# WIFI.net
KiCad netlist of a schematic drawn in Altium Designer
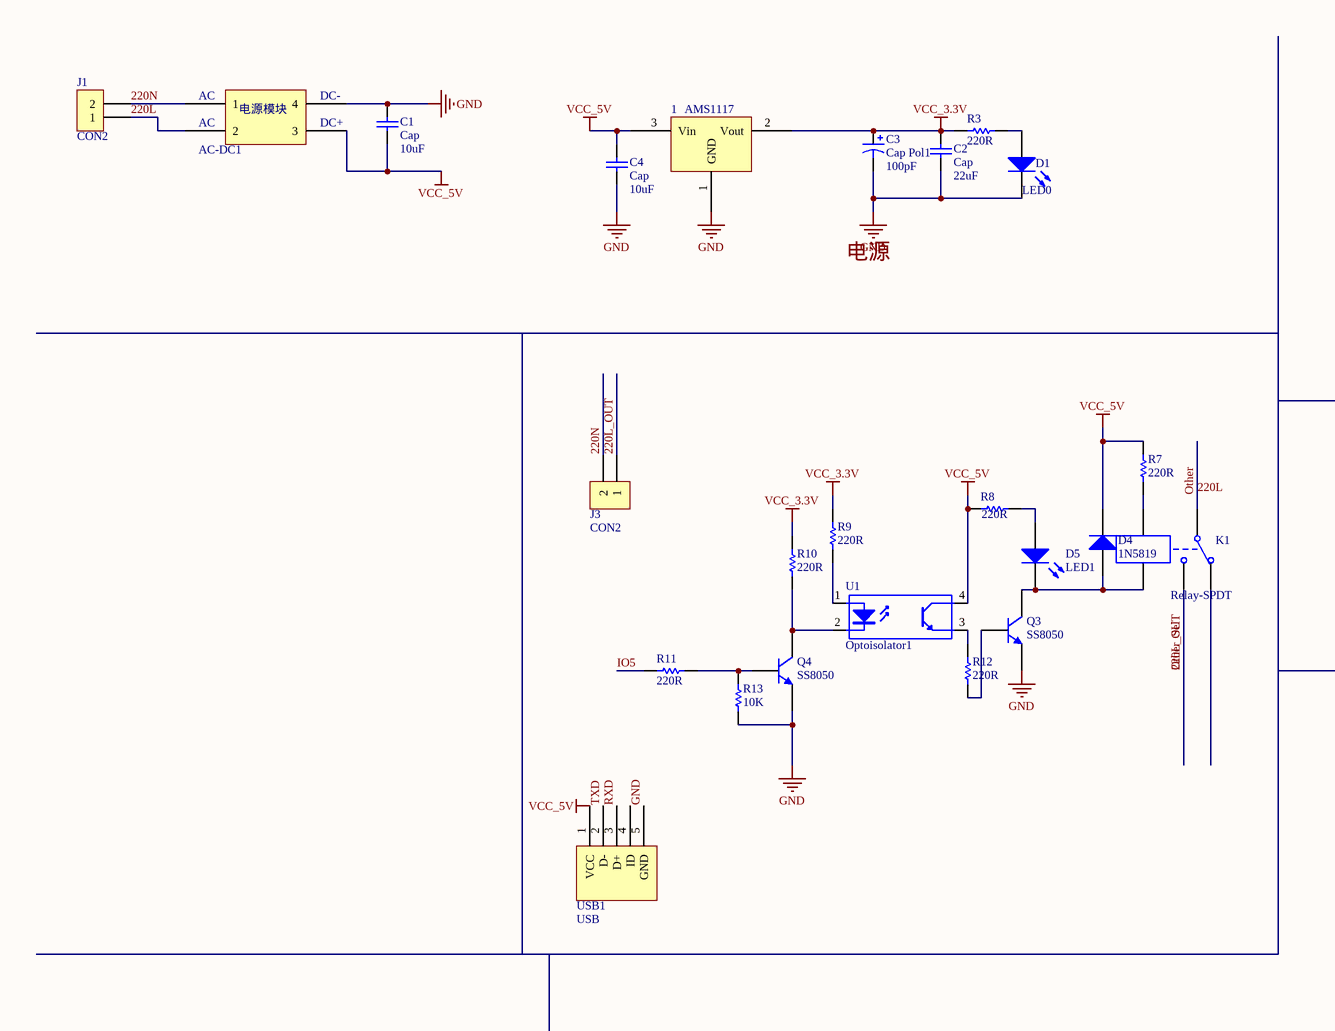
[diagram p0: WIFI.SchDoc, left]
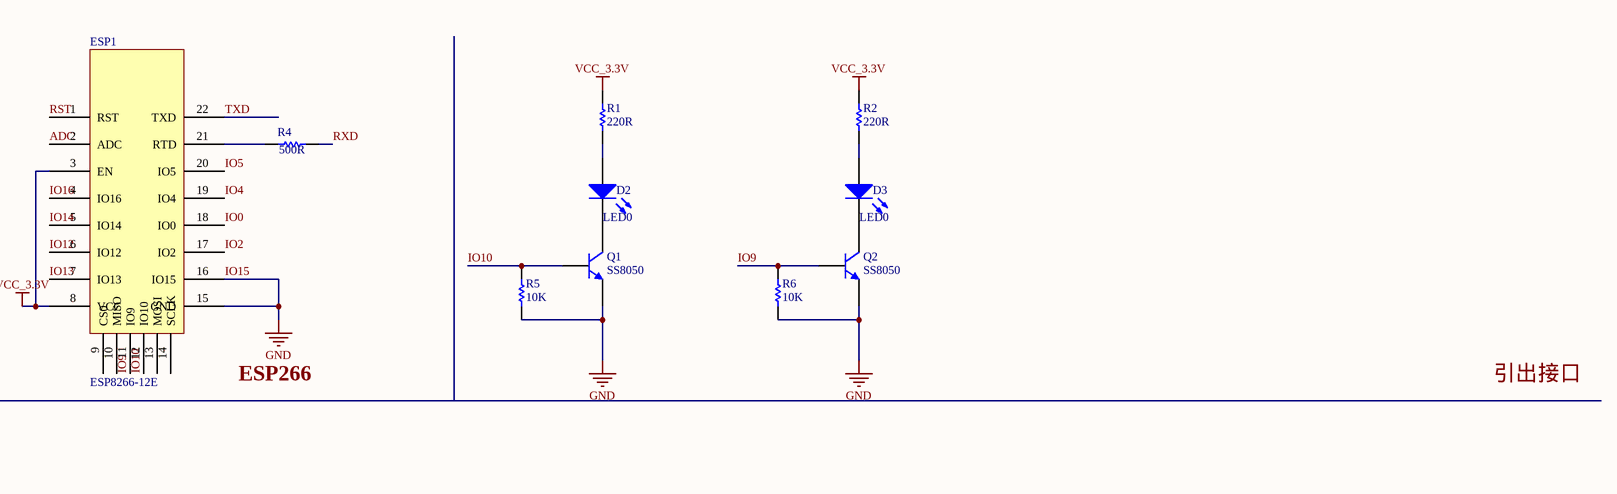
[diagram p1: WIFI.SchDoc, right]

(export (version "E")
  (design (tool "Eeschema 10.0.6"))
  (components
    (comp (ref "1") (value "AMS1117") (footprint "SOT223") (libsource (lib "开关电路") (part "AMS1117")))
    (comp (ref "AC-DC1") (value "220—5") (footprint "POWER-220_5") (libsource (lib "开关电路") (part "220—5")))
    (comp (ref "C1")
      (value "Cap")
      (footprint "CAP-E SMD 8X8")
      (description "Capacitor")
      (fields (field (name "ALTIUM_VALUE") "10uF") (field (name "PUBLISHER") "Altium Limited"))
      (libsource (lib "Miscellaneous Devices0") (part "Cap"))
    )
    (comp (ref "C2")
      (value "Cap")
      (footprint "1206")
      (description "Capacitor")
      (fields (field (name "ALTIUM_VALUE") "22uF") (field (name "PUBLISHER") "Altium Limited"))
      (libsource (lib "Miscellaneous Devices0") (part "Cap"))
    )
    (comp (ref "C3")
      (value "Cap Pol1")
      (footprint "CAP-E SMD 8X8")
      (description "Polarized Capacitor (Radial)")
      (fields (field (name "ALTIUM_VALUE") "100pF") (field (name "PUBLISHER") "Altium Limited"))
      (libsource (lib "Miscellaneous Devices") (part "Cap Pol1"))
    )
    (comp (ref "C4")
      (value "Cap")
      (footprint "1206")
      (description "Capacitor")
      (fields (field (name "ALTIUM_VALUE") "10uF") (field (name "PUBLISHER") "Altium Limited"))
      (libsource (lib "Miscellaneous Devices0") (part "Cap"))
    )
    (comp (ref "D1")
      (value "LED0")
      (footprint "ZH常用封装ZH:LED0805")
      (description "Typical INFRARED GaAs LED")
      (fields (field (name "PUBLISHER") "Altium Limited"))
      (libsource (lib "Miscellaneous Devices") (part "LED0"))
    )
    (comp (ref "D2")
      (value "LED0")
      (footprint "ZH常用封装ZH:LED0805")
      (description "Typical INFRARED GaAs LED")
      (fields (field (name "PUBLISHER") "Altium Limited"))
      (libsource (lib "Miscellaneous Devices") (part "LED0"))
    )
    (comp (ref "D3")
      (value "LED0")
      (footprint "ZH常用封装ZH:LED0805")
      (description "Typical INFRARED GaAs LED")
      (fields (field (name "PUBLISHER") "Altium Limited"))
      (libsource (lib "Miscellaneous Devices") (part "LED0"))
    )
    (comp (ref "D4")
      (value "1N5819")
      (footprint "ZH常用封装ZH:DO-214AC/SMA")
      (description "Default Diode")
      (fields (field (name "PUBLISHER") "Altium Limited"))
      (libsource (lib "Miscellaneous Devices") (part "Diode"))
    )
    (comp (ref "D5")
      (value "LED1")
      (footprint "ZH常用封装ZH:LED0805")
      (description "Typical RED GaAs LED")
      (fields (field (name "PUBLISHER") "Altium Limited"))
      (libsource (lib "Miscellaneous Devices") (part "LED1"))
    )
    (comp (ref "ESP1")
      (value "ESP8266-12E")
      (footprint "ZH常用封装ZH:ESP8266")
      (libsource (lib "开关电路") (part "ESP8266"))
    )
    (comp (ref "J1")
      (value "CON2")
      (footprint "TML-2-5.08")
      (description "Connector")
      (libsource (lib "") (part "CON2_1"))
    )
    (comp (ref "J3")
      (value "CON2")
      (footprint "TML-2-5.08")
      (description "Connector")
      (libsource (lib "插件") (part "CON2"))
    )
    (comp (ref "K1")
      (value "Relay-SPDT")
      (footprint "5V-5")
      (description "Single-Pole Dual-Throw Relay")
      (fields (field (name "PUBLISHER") "Altium Limited"))
      (libsource (lib "Miscellaneous Devices") (part "Relay-SPDT"))
    )
    (comp (ref "Q1")
      (value "SS8050")
      (footprint "SOT-23")
      (description "NPN General Purpose Amplifier")
      (fields (field (name "PUBLISHER") "Altium Limited"))
      (libsource (lib "Miscellaneous Devices") (part "2N3904"))
    )
    (comp (ref "Q2")
      (value "SS8050")
      (footprint "SOT-23")
      (description "NPN General Purpose Amplifier")
      (fields (field (name "PUBLISHER") "Altium Limited"))
      (libsource (lib "Miscellaneous Devices") (part "2N3904"))
    )
    (comp (ref "Q3")
      (value "SS8050")
      (footprint "SOT-23")
      (description "NPN General Purpose Amplifier")
      (fields (field (name "PUBLISHER") "Altium Limited"))
      (libsource (lib "Miscellaneous Devices") (part "2N3904"))
    )
    (comp (ref "Q4")
      (value "SS8050")
      (footprint "SOT-23")
      (description "NPN General Purpose Amplifier")
      (fields (field (name "PUBLISHER") "Altium Limited"))
      (libsource (lib "Miscellaneous Devices") (part "2N3904"))
    )
    (comp (ref "R1")
      (value "220R")
      (footprint "贴片:0805")
      (description "Resistor")
      (fields (field (name "Comment") "Res") (field (name "PUBLISHER") "Altium Limited"))
      (libsource (lib "电阻电容") (part "Res"))
    )
    (comp (ref "R2")
      (value "220R")
      (footprint "贴片:0805")
      (description "Resistor")
      (fields (field (name "Comment") "Res") (field (name "PUBLISHER") "Altium Limited"))
      (libsource (lib "电阻电容") (part "Res"))
    )
    (comp (ref "R3")
      (value "220R")
      (footprint "贴片:0805")
      (description "Resistor")
      (fields (field (name "Comment") "Res") (field (name "PUBLISHER") "Altium Limited"))
      (libsource (lib "电阻电容") (part "Res"))
    )
    (comp (ref "R4")
      (value "500R")
      (footprint "贴片:0805")
      (description "Resistor")
      (fields (field (name "Comment") "Res") (field (name "PUBLISHER") "Altium Limited"))
      (libsource (lib "电阻电容") (part "Res"))
    )
    (comp (ref "R5")
      (value "10K")
      (footprint "贴片:0805")
      (description "Resistor")
      (fields (field (name "Comment") "Res") (field (name "PUBLISHER") "Altium Limited"))
      (libsource (lib "电阻电容") (part "Res"))
    )
    (comp (ref "R6")
      (value "10K")
      (footprint "贴片:0805")
      (description "Resistor")
      (fields (field (name "Comment") "Res") (field (name "PUBLISHER") "Altium Limited"))
      (libsource (lib "电阻电容") (part "Res"))
    )
    (comp (ref "R7")
      (value "220R")
      (footprint "贴片:0805")
      (description "Resistor")
      (fields (field (name "Comment") "Res") (field (name "PUBLISHER") "Altium Limited"))
      (libsource (lib "电阻电容") (part "Res"))
    )
    (comp (ref "R8")
      (value "220R")
      (footprint "贴片:0805")
      (description "Resistor")
      (fields (field (name "Comment") "Res") (field (name "PUBLISHER") "Altium Limited"))
      (libsource (lib "电阻电容") (part "Res"))
    )
    (comp (ref "R9")
      (value "220R")
      (footprint "贴片:0805")
      (description "Resistor")
      (fields (field (name "Comment") "Res") (field (name "PUBLISHER") "Altium Limited"))
      (libsource (lib "电阻电容") (part "Res"))
    )
    (comp (ref "R10")
      (value "220R")
      (footprint "贴片:0805")
      (description "Resistor")
      (fields (field (name "Comment") "Res") (field (name "PUBLISHER") "Altium Limited"))
      (libsource (lib "电阻电容") (part "Res"))
    )
    (comp (ref "R11")
      (value "220R")
      (footprint "贴片:0805")
      (description "Resistor")
      (fields (field (name "Comment") "Res") (field (name "PUBLISHER") "Altium Limited"))
      (libsource (lib "电阻电容") (part "Res"))
    )
    (comp (ref "R12")
      (value "220R")
      (footprint "贴片:0805")
      (description "Resistor")
      (fields (field (name "Comment") "Res") (field (name "PUBLISHER") "Altium Limited"))
      (libsource (lib "电阻电容") (part "Res"))
    )
    (comp (ref "R13")
      (value "10K")
      (footprint "贴片:0805")
      (description "Resistor")
      (fields (field (name "Comment") "Res") (field (name "PUBLISHER") "Altium Limited"))
      (libsource (lib "电阻电容") (part "Res"))
    )
    (comp (ref "U1")
      (value "Optoisolator1")
      (footprint "DIP4")
      (description "4-Pin Phototransistor Optocoupler")
      (fields (field (name "PUBLISHER") "Altium Limited"))
      (libsource (lib "Miscellaneous Devices") (part "Optoisolator1"))
    )
    (comp (ref "USB1")
      (value "USB")
      (footprint "ZH常用封装ZH:USB-MINI")
      (libsource (lib "CH340") (part "miniUSB-b"))
    )
  )
  (nets
    (net (code "1") (name "/220L") (class "Default")
      (node (ref "AC-DC1") (pin "2") (pinfunction "2_2") (pintype "passive"))
      (node (ref "J1") (pin "1") (pinfunction "1_1") (pintype "passive"))
      (node (ref "K1") (pin "1") (pinfunction "1_1") (pintype "passive"))
    )
    (net (code "2") (name "/220L_OUT") (class "Default")
      (node (ref "J3") (pin "1") (pinfunction "1_1") (pintype "passive"))
      (node (ref "K1") (pin "3") (pinfunction "3_3") (pintype "passive"))
    )
    (net (code "3") (name "/220N") (class "Default")
      (node (ref "AC-DC1") (pin "1") (pinfunction "1_1") (pintype "passive"))
      (node (ref "J1") (pin "2") (pinfunction "2_2") (pintype "passive"))
      (node (ref "J3") (pin "2") (pinfunction "2_2") (pintype "passive"))
    )
    (net (code "5") (name "/ADC") (class "Default")
      (node (ref "ESP1") (pin "2") (pinfunction "ADC_2") (pintype "passive"))
    )
    (net (code "7") (name "/IO0") (class "Default")
      (node (ref "ESP1") (pin "18") (pinfunction "IO0_18") (pintype "passive"))
    )
    (net (code "8") (name "/IO2") (class "Default")
      (node (ref "ESP1") (pin "17") (pinfunction "IO2_17") (pintype "passive"))
    )
    (net (code "9") (name "/IO4") (class "Default")
      (node (ref "ESP1") (pin "19") (pinfunction "IO4_19") (pintype "passive"))
    )
    (net (code "10") (name "/IO5") (class "Default")
      (node (ref "ESP1") (pin "20") (pinfunction "IO5_20") (pintype "passive"))
      (node (ref "R11") (pin "2") (pinfunction "2_2") (pintype "passive"))
    )
    (net (code "11") (name "/IO9") (class "Default")
      (node (ref "ESP1") (pin "11") (pinfunction "IO9_11") (pintype "passive"))
      (node (ref "Q2") (pin "2") (pinfunction "B_2") (pintype "passive"))
      (node (ref "R6") (pin "2") (pinfunction "2_2") (pintype "passive"))
    )
    (net (code "12") (name "/IO10") (class "Default")
      (node (ref "ESP1") (pin "12") (pinfunction "IO10_12") (pintype "passive"))
      (node (ref "Q1") (pin "2") (pinfunction "B_2") (pintype "passive"))
      (node (ref "R5") (pin "2") (pinfunction "2_2") (pintype "passive"))
    )
    (net (code "13") (name "/IO12") (class "Default")
      (node (ref "ESP1") (pin "6") (pinfunction "IO12_6") (pintype "passive"))
    )
    (net (code "14") (name "/IO13") (class "Default")
      (node (ref "ESP1") (pin "7") (pinfunction "IO13_7") (pintype "passive"))
    )
    (net (code "15") (name "/IO14") (class "Default")
      (node (ref "ESP1") (pin "5") (pinfunction "IO14_5") (pintype "passive"))
    )
    (net (code "16") (name "/IO16") (class "Default")
      (node (ref "ESP1") (pin "4") (pinfunction "IO16_4") (pintype "passive"))
    )
    (net (code "17") (name "/RST") (class "Default")
      (node (ref "ESP1") (pin "1") (pinfunction "RST_1") (pintype "passive"))
    )
    (net (code "18") (name "/RXD") (class "Default")
      (node (ref "R4") (pin "2") (pinfunction "2_2") (pintype "passive"))
      (node (ref "USB1") (pin "3") (pinfunction "D+_3") (pintype "passive"))
    )
    (net (code "19") (name "/TXD") (class "Default")
      (node (ref "ESP1") (pin "22") (pinfunction "TXD_22") (pintype "passive"))
      (node (ref "USB1") (pin "2") (pinfunction "D-_2") (pintype "passive"))
    )
    (net (code "22") (name "GND") (class "Default")
      (node (ref "1") (pin "1") (pinfunction "GND_1") (pintype "passive"))
      (node (ref "AC-DC1") (pin "4") (pinfunction "4_4") (pintype "passive"))
      (node (ref "C1") (pin "1") (pinfunction "1_1") (pintype "passive"))
      (node (ref "C2") (pin "2") (pinfunction "2_2") (pintype "passive"))
      (node (ref "C3") (pin "2") (pinfunction "2_2") (pintype "passive"))
      (node (ref "C4") (pin "2") (pinfunction "2_2") (pintype "passive"))
      (node (ref "D1") (pin "2") (pinfunction "K_2") (pintype "passive"))
      (node (ref "ESP1") (pin "15") (pinfunction "GND_15") (pintype "passive"))
      (node (ref "ESP1") (pin "16") (pinfunction "IO15_16") (pintype "passive"))
      (node (ref "Q1") (pin "1") (pinfunction "E_1") (pintype "passive"))
      (node (ref "Q2") (pin "1") (pinfunction "E_1") (pintype "passive"))
      (node (ref "Q3") (pin "1") (pinfunction "E_1") (pintype "passive"))
      (node (ref "Q4") (pin "1") (pinfunction "E_1") (pintype "passive"))
      (node (ref "R13") (pin "1") (pinfunction "1_1") (pintype "passive"))
      (node (ref "R5") (pin "1") (pinfunction "1_1") (pintype "passive"))
      (node (ref "R6") (pin "1") (pinfunction "1_1") (pintype "passive"))
      (node (ref "USB1") (pin "5") (pinfunction "GND_5") (pintype "passive"))
    )
    (net (code "23") (name "Net-(D1-A)") (class "Default")
      (node (ref "D1") (pin "1") (pinfunction "A_1") (pintype "passive"))
      (node (ref "R3") (pin "1") (pinfunction "1_1") (pintype "passive"))
    )
    (net (code "24") (name "Net-(D2-A)") (class "Default")
      (node (ref "D2") (pin "1") (pinfunction "A_1") (pintype "passive"))
      (node (ref "R1") (pin "2") (pinfunction "2_2") (pintype "passive"))
    )
    (net (code "25") (name "Net-(D2-K)") (class "Default")
      (node (ref "D2") (pin "2") (pinfunction "K_2") (pintype "passive"))
      (node (ref "Q1") (pin "3") (pinfunction "C_3") (pintype "passive"))
    )
    (net (code "26") (name "Net-(D3-A)") (class "Default")
      (node (ref "D3") (pin "1") (pinfunction "A_1") (pintype "passive"))
      (node (ref "R2") (pin "2") (pinfunction "2_2") (pintype "passive"))
    )
    (net (code "27") (name "Net-(D3-K)") (class "Default")
      (node (ref "D3") (pin "2") (pinfunction "K_2") (pintype "passive"))
      (node (ref "Q2") (pin "3") (pinfunction "C_3") (pintype "passive"))
    )
    (net (code "28") (name "Net-(D4-A)") (class "Default")
      (node (ref "D4") (pin "1") (pinfunction "A_1") (pintype "passive"))
      (node (ref "D5") (pin "2") (pinfunction "K_2") (pintype "passive"))
      (node (ref "K1") (pin "5") (pinfunction "5_5") (pintype "passive"))
      (node (ref "Q3") (pin "3") (pinfunction "C_3") (pintype "passive"))
    )
    (net (code "29") (name "Net-(D5-A)") (class "Default")
      (node (ref "D5") (pin "1") (pinfunction "A_1") (pintype "passive"))
      (node (ref "R8") (pin "2") (pinfunction "2_2") (pintype "passive"))
    )
    (net (code "30") (name "Net-(ESP1-RTD)") (class "Default")
      (node (ref "ESP1") (pin "21") (pinfunction "RTD_21") (pintype "passive"))
      (node (ref "R4") (pin "1") (pinfunction "1_1") (pintype "passive"))
    )
    (net (code "31") (name "Net-(K1-Pad4)") (class "Default")
      (node (ref "K1") (pin "4") (pinfunction "4_4") (pintype "passive"))
      (node (ref "R7") (pin "1") (pinfunction "1_1") (pintype "passive"))
    )
    (net (code "32") (name "Net-(Q3-B)") (class "Default")
      (node (ref "Q3") (pin "2") (pinfunction "B_2") (pintype "passive"))
      (node (ref "R12") (pin "1") (pinfunction "1_1") (pintype "passive"))
    )
    (net (code "33") (name "Net-(Q4-B)") (class "Default")
      (node (ref "Q4") (pin "2") (pinfunction "B_2") (pintype "passive"))
      (node (ref "R11") (pin "1") (pinfunction "1_1") (pintype "passive"))
      (node (ref "R13") (pin "2") (pinfunction "2_2") (pintype "passive"))
    )
    (net (code "34") (name "Net-(Q4-C)") (class "Default")
      (node (ref "Q4") (pin "3") (pinfunction "C_3") (pintype "passive"))
      (node (ref "R10") (pin "1") (pinfunction "1_1") (pintype "passive"))
      (node (ref "U1") (pin "2") (pinfunction "K_2") (pintype "passive"))
    )
    (net (code "35") (name "Net-(U1-A)") (class "Default")
      (node (ref "R9") (pin "1") (pinfunction "1_1") (pintype "passive"))
      (node (ref "U1") (pin "1") (pinfunction "A_1") (pintype "passive"))
    )
    (net (code "36") (name "Net-(U1-E)") (class "Default")
      (node (ref "R12") (pin "2") (pinfunction "2_2") (pintype "passive"))
      (node (ref "U1") (pin "3") (pinfunction "E_3") (pintype "passive"))
    )
    (net (code "37") (name "VCC_3.3V") (class "Default")
      (node (ref "1") (pin "2") (pinfunction "Vout_2") (pintype "passive"))
      (node (ref "C2") (pin "1") (pinfunction "1_1") (pintype "passive"))
      (node (ref "C3") (pin "1") (pinfunction "1_1") (pintype "passive"))
      (node (ref "ESP1") (pin "3") (pinfunction "EN_3") (pintype "passive"))
      (node (ref "ESP1") (pin "8") (pinfunction "VCC_8") (pintype "passive"))
      (node (ref "R1") (pin "1") (pinfunction "1_1") (pintype "passive"))
      (node (ref "R10") (pin "2") (pinfunction "2_2") (pintype "passive"))
      (node (ref "R2") (pin "1") (pinfunction "1_1") (pintype "passive"))
      (node (ref "R3") (pin "2") (pinfunction "2_2") (pintype "passive"))
      (node (ref "R9") (pin "2") (pinfunction "2_2") (pintype "passive"))
    )
    (net (code "38") (name "VCC_5V") (class "Default")
      (node (ref "1") (pin "3") (pinfunction "Vin_3") (pintype "passive"))
      (node (ref "AC-DC1") (pin "3") (pinfunction "3_3") (pintype "passive"))
      (node (ref "C1") (pin "2") (pinfunction "2_2") (pintype "passive"))
      (node (ref "C4") (pin "1") (pinfunction "1_1") (pintype "passive"))
      (node (ref "D4") (pin "2") (pinfunction "K_2") (pintype "passive"))
      (node (ref "R7") (pin "2") (pinfunction "2_2") (pintype "passive"))
      (node (ref "R8") (pin "1") (pinfunction "1_1") (pintype "passive"))
      (node (ref "U1") (pin "4") (pinfunction "C_4") (pintype "passive"))
      (node (ref "USB1") (pin "1") (pinfunction "VCC_1") (pintype "passive"))
    )
    (net (code "39") (name "unconnected-(ESP1-CS0-Pad9)") (class "Default")
      (node (ref "ESP1") (pin "9") (pinfunction "CS0_9") (pintype "passive"))
    )
    (net (code "40") (name "unconnected-(ESP1-MISO-Pad10)") (class "Default")
      (node (ref "ESP1") (pin "10") (pinfunction "MISO_10") (pintype "passive"))
    )
    (net (code "41") (name "unconnected-(ESP1-MOSI-Pad13)") (class "Default")
      (node (ref "ESP1") (pin "13") (pinfunction "MOSI_13") (pintype "passive"))
    )
    (net (code "42") (name "unconnected-(ESP1-SCLK-Pad14)") (class "Default")
      (node (ref "ESP1") (pin "14") (pinfunction "SCLK_14") (pintype "passive"))
    )
    (net (code "43") (name "unconnected-(K1-Pad2)") (class "Default")
      (node (ref "K1") (pin "2") (pinfunction "2_2") (pintype "passive"))
    )
    (net (code "44") (name "unconnected-(USB1-ID-Pad4)") (class "Default")
      (node (ref "USB1") (pin "4") (pinfunction "ID_4") (pintype "passive"))
    )
  )
)
